# WizHorizonObserver.net
KiCad netlist of a schematic drawn in EAGLE
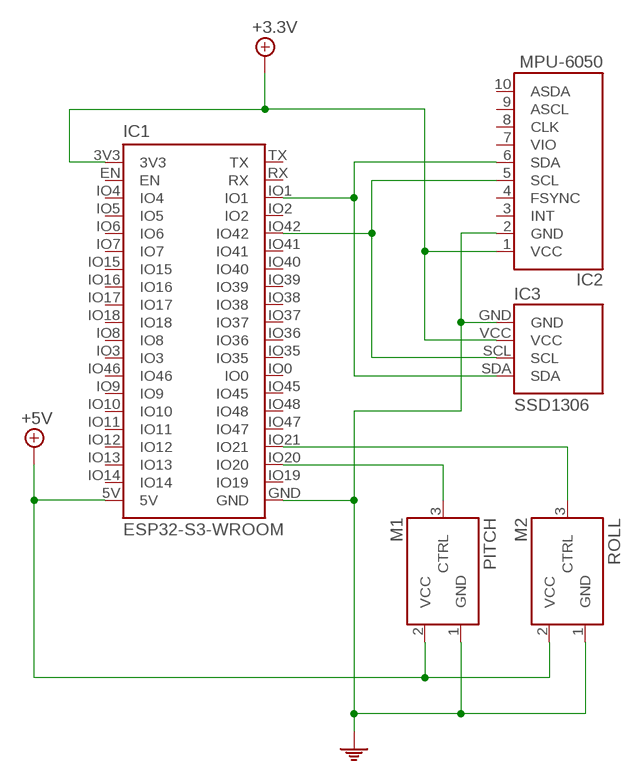
[diagram p0: schematic, sheet 1]

(export (version "E")
  (design (tool "Eeschema 10.0.6"))
  (components
    (comp (ref "IC1")
      (value "ESP32-S3-WROOM")
      (footprint "eagle-import:ESP32-S3-WROOM")
      (libsource (lib "eagle-import") (part "ESP32-S3-WROOM"))
    )
    (comp (ref "IC2")
      (value "MPU-6050")
      (footprint "eagle-import:SIL10")
      (libsource (lib "eagle-import") (part "MPU-6050SIL10"))
    )
    (comp (ref "IC3")
      (value "SSD1306")
      (footprint "eagle-import:SSD1306")
      (libsource (lib "eagle-import") (part "SSD1306"))
    )
    (comp (ref "M1")
      (value "PITCH")
      (footprint "eagle-import:SIL3")
      (libsource (lib "eagle-import") (part "SERVO-MOTORSIL3"))
    )
    (comp (ref "M2")
      (value "ROLL")
      (footprint "eagle-import:SIL3")
      (libsource (lib "eagle-import") (part "SERVO-MOTORSIL3"))
    )
  )
  (nets
    (net (code "1") (name "+3.3V") (class "Default")
      (node (ref "IC1") (pin "3V3") (pinfunction "3V3_3V3") (pintype "power_in"))
      (node (ref "IC2") (pin "1") (pinfunction "VCC_1") (pintype "power_in"))
      (node (ref "IC3") (pin "VCC") (pinfunction "VCC_VCC") (pintype "power_in"))
    )
    (net (code "2") (name "+5V") (class "Default")
      (node (ref "IC1") (pin "5V") (pinfunction "5V_5V") (pintype "power_in"))
      (node (ref "M1") (pin "2") (pinfunction "VCC_2") (pintype "power_in"))
      (node (ref "M2") (pin "2") (pinfunction "VCC_2") (pintype "power_in"))
    )
    (net (code "3") (name "GND") (class "Default")
      (node (ref "IC1") (pin "GND") (pinfunction "GND_GND") (pintype "power_in"))
      (node (ref "IC2") (pin "2") (pinfunction "GND_2") (pintype "power_in"))
      (node (ref "IC3") (pin "GND") (pinfunction "GND_GND") (pintype "power_in"))
      (node (ref "M1") (pin "1") (pinfunction "GND_1") (pintype "power_in"))
      (node (ref "M2") (pin "1") (pinfunction "GND_1") (pintype "power_in"))
    )
    (net (code "4") (name "Net-(IC2-SCL)") (class "Default")
      (node (ref "IC1") (pin "IO42") (pinfunction "IO42_IO42") (pintype "bidirectional"))
      (node (ref "IC2") (pin "5") (pinfunction "SCL_5") (pintype "bidirectional"))
      (node (ref "IC3") (pin "SCL") (pinfunction "SCL_SCL") (pintype "bidirectional"))
    )
    (net (code "5") (name "Net-(IC2-SDA)") (class "Default")
      (node (ref "IC1") (pin "IO1") (pinfunction "IO1_IO1") (pintype "bidirectional"))
      (node (ref "IC2") (pin "6") (pinfunction "SDA_6") (pintype "bidirectional"))
      (node (ref "IC3") (pin "SDA") (pinfunction "SDA_SDA") (pintype "bidirectional"))
    )
    (net (code "6") (name "Net-(M1-CTRL)") (class "Default")
      (node (ref "IC1") (pin "IO20") (pinfunction "IO20_IO20") (pintype "bidirectional"))
      (node (ref "M1") (pin "3") (pinfunction "CTRL_3") (pintype "input"))
    )
    (net (code "7") (name "Net-(M2-CTRL)") (class "Default")
      (node (ref "IC1") (pin "IO21") (pinfunction "IO21_IO21") (pintype "bidirectional"))
      (node (ref "M2") (pin "3") (pinfunction "CTRL_3") (pintype "input"))
    )
    (net (code "8") (name "unconnected-(IC1-PadEN)") (class "Default")
      (node (ref "IC1") (pin "EN") (pinfunction "EN_EN") (pintype "input"))
    )
    (net (code "9") (name "unconnected-(IC1-PadIO0)") (class "Default")
      (node (ref "IC1") (pin "IO0") (pinfunction "IO0_IO0") (pintype "bidirectional"))
    )
    (net (code "10") (name "unconnected-(IC1-PadIO2)") (class "Default")
      (node (ref "IC1") (pin "IO2") (pinfunction "IO2_IO2") (pintype "bidirectional"))
    )
    (net (code "11") (name "unconnected-(IC1-PadIO3)") (class "Default")
      (node (ref "IC1") (pin "IO3") (pinfunction "IO3_IO3") (pintype "bidirectional"))
    )
    (net (code "12") (name "unconnected-(IC1-PadIO4)") (class "Default")
      (node (ref "IC1") (pin "IO4") (pinfunction "IO4_IO4") (pintype "bidirectional"))
    )
    (net (code "13") (name "unconnected-(IC1-PadIO5)") (class "Default")
      (node (ref "IC1") (pin "IO5") (pinfunction "IO5_IO5") (pintype "bidirectional"))
    )
    (net (code "14") (name "unconnected-(IC1-PadIO6)") (class "Default")
      (node (ref "IC1") (pin "IO6") (pinfunction "IO6_IO6") (pintype "bidirectional"))
    )
    (net (code "15") (name "unconnected-(IC1-PadIO7)") (class "Default")
      (node (ref "IC1") (pin "IO7") (pinfunction "IO7_IO7") (pintype "bidirectional"))
    )
    (net (code "16") (name "unconnected-(IC1-PadIO8)") (class "Default")
      (node (ref "IC1") (pin "IO8") (pinfunction "IO8_IO8") (pintype "bidirectional"))
    )
    (net (code "17") (name "unconnected-(IC1-PadIO9)") (class "Default")
      (node (ref "IC1") (pin "IO9") (pinfunction "IO9_IO9") (pintype "bidirectional"))
    )
    (net (code "18") (name "unconnected-(IC1-PadIO10)") (class "Default")
      (node (ref "IC1") (pin "IO10") (pinfunction "IO10_IO10") (pintype "bidirectional"))
    )
    (net (code "19") (name "unconnected-(IC1-PadIO11)") (class "Default")
      (node (ref "IC1") (pin "IO11") (pinfunction "IO11_IO11") (pintype "bidirectional"))
    )
    (net (code "20") (name "unconnected-(IC1-PadIO12)") (class "Default")
      (node (ref "IC1") (pin "IO12") (pinfunction "IO12_IO12") (pintype "bidirectional"))
    )
    (net (code "21") (name "unconnected-(IC1-PadIO13)") (class "Default")
      (node (ref "IC1") (pin "IO13") (pinfunction "IO13_IO13") (pintype "bidirectional"))
    )
    (net (code "22") (name "unconnected-(IC1-PadIO14)") (class "Default")
      (node (ref "IC1") (pin "IO14") (pinfunction "IO14_IO14") (pintype "bidirectional"))
    )
    (net (code "23") (name "unconnected-(IC1-PadIO15)") (class "Default")
      (node (ref "IC1") (pin "IO15") (pinfunction "IO15_IO15") (pintype "bidirectional"))
    )
    (net (code "24") (name "unconnected-(IC1-PadIO16)") (class "Default")
      (node (ref "IC1") (pin "IO16") (pinfunction "IO16_IO16") (pintype "bidirectional"))
    )
    (net (code "25") (name "unconnected-(IC1-PadIO17)") (class "Default")
      (node (ref "IC1") (pin "IO17") (pinfunction "IO17_IO17") (pintype "bidirectional"))
    )
    (net (code "26") (name "unconnected-(IC1-PadIO18)") (class "Default")
      (node (ref "IC1") (pin "IO18") (pinfunction "IO18_IO18") (pintype "bidirectional"))
    )
    (net (code "27") (name "unconnected-(IC1-PadIO19)") (class "Default")
      (node (ref "IC1") (pin "IO19") (pinfunction "IO19_IO19") (pintype "bidirectional"))
    )
    (net (code "28") (name "unconnected-(IC1-PadIO35)") (class "Default")
      (node (ref "IC1") (pin "IO35") (pinfunction "IO35_IO35") (pintype "bidirectional"))
    )
    (net (code "29") (name "unconnected-(IC1-PadIO36)") (class "Default")
      (node (ref "IC1") (pin "IO36") (pinfunction "IO36_IO36") (pintype "bidirectional"))
    )
    (net (code "30") (name "unconnected-(IC1-PadIO37)") (class "Default")
      (node (ref "IC1") (pin "IO37") (pinfunction "IO37_IO37") (pintype "bidirectional"))
    )
    (net (code "31") (name "unconnected-(IC1-PadIO38)") (class "Default")
      (node (ref "IC1") (pin "IO38") (pinfunction "IO38_IO38") (pintype "bidirectional"))
    )
    (net (code "32") (name "unconnected-(IC1-PadIO39)") (class "Default")
      (node (ref "IC1") (pin "IO39") (pinfunction "IO39_IO39") (pintype "bidirectional"))
    )
    (net (code "33") (name "unconnected-(IC1-PadIO40)") (class "Default")
      (node (ref "IC1") (pin "IO40") (pinfunction "IO40_IO40") (pintype "bidirectional"))
    )
    (net (code "34") (name "unconnected-(IC1-PadIO41)") (class "Default")
      (node (ref "IC1") (pin "IO41") (pinfunction "IO41_IO41") (pintype "bidirectional"))
    )
    (net (code "35") (name "unconnected-(IC1-PadIO45)") (class "Default")
      (node (ref "IC1") (pin "IO45") (pinfunction "IO45_IO45") (pintype "bidirectional"))
    )
    (net (code "36") (name "unconnected-(IC1-PadIO46)") (class "Default")
      (node (ref "IC1") (pin "IO46") (pinfunction "IO46_IO46") (pintype "bidirectional"))
    )
    (net (code "37") (name "unconnected-(IC1-PadIO47)") (class "Default")
      (node (ref "IC1") (pin "IO47") (pinfunction "IO47_IO47") (pintype "bidirectional"))
    )
    (net (code "38") (name "unconnected-(IC1-PadIO48)") (class "Default")
      (node (ref "IC1") (pin "IO48") (pinfunction "IO48_IO48") (pintype "bidirectional"))
    )
    (net (code "39") (name "unconnected-(IC1-PadRX)") (class "Default")
      (node (ref "IC1") (pin "RX") (pinfunction "RX_RX") (pintype "bidirectional"))
    )
    (net (code "40") (name "unconnected-(IC1-PadTX)") (class "Default")
      (node (ref "IC1") (pin "TX") (pinfunction "TX_TX") (pintype "bidirectional"))
    )
    (net (code "41") (name "unconnected-(IC2-ASCL-Pad9)") (class "Default")
      (node (ref "IC2") (pin "9") (pinfunction "ASCL_9") (pintype "bidirectional"))
    )
    (net (code "42") (name "unconnected-(IC2-ASDA-Pad10)") (class "Default")
      (node (ref "IC2") (pin "10") (pinfunction "ASDA_10") (pintype "bidirectional"))
    )
    (net (code "43") (name "unconnected-(IC2-CLK-Pad8)") (class "Default")
      (node (ref "IC2") (pin "8") (pinfunction "CLK_8") (pintype "bidirectional"))
    )
    (net (code "44") (name "unconnected-(IC2-FSYNC-Pad4)") (class "Default")
      (node (ref "IC2") (pin "4") (pinfunction "FSYNC_4") (pintype "bidirectional"))
    )
    (net (code "45") (name "unconnected-(IC2-INT-Pad3)") (class "Default")
      (node (ref "IC2") (pin "3") (pinfunction "INT_3") (pintype "bidirectional"))
    )
    (net (code "46") (name "unconnected-(IC2-VIO-Pad7)") (class "Default")
      (node (ref "IC2") (pin "7") (pinfunction "VIO_7") (pintype "bidirectional"))
    )
  )
)
